# AntiStartingCrap.net
KiCad netlist of a schematic drawn in Altium Designer
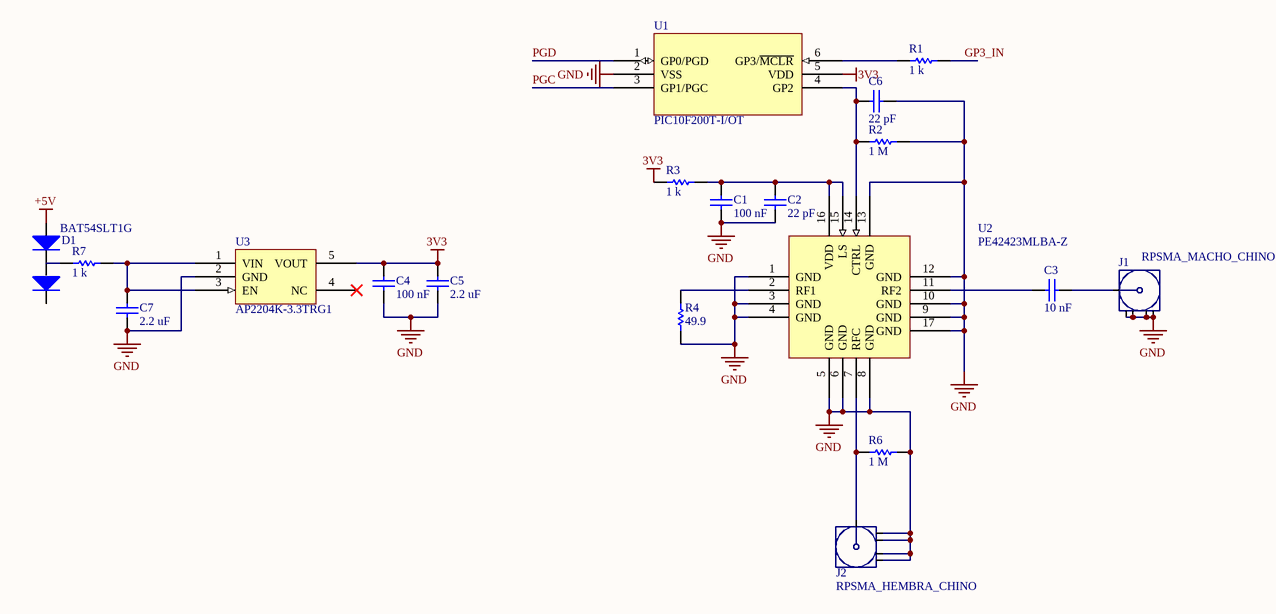
[diagram p0: AntiStartingCrap.SchDoc]

(export (version "E")
  (design (tool "Eeschema 10.0.6"))
  (components
    (comp (ref "C1")
      (value "100 nF")
      (footprint "CAPC1608X10L")
      (description "CAP CER 0.1UF 25V X7R 0603")
      (fields
        (field (name "MANUFACTURER") "Samsung Electro-Mechanics America, Inc.")
        (field (name "MANUFACTURER PART NUMBER") "CL10B104KA8NNNC")
      )
      (libsource (lib "Componentes") (part "CL10B104KA8NNNC"))
    )
    (comp (ref "C2")
      (value "22 pF")
      (footprint "CAPC1608X10L")
      (description "CAP CER 22PF 50V NP0 0603")
      (fields
        (field (name "MANUFACTURER") "Murata Electronics North America")
        (field (name "MANUFACTURER PART NUMBER") "GCM1885C1H220JA16D")
      )
      (libsource (lib "Componentes") (part "GCM1885C1H220JA16D"))
    )
    (comp (ref "C3")
      (value "10 nF")
      (footprint "CAPC1608X10L")
      (description "CAP CER 10000PF 50V NP0 0603")
      (fields
        (field (name "MANUFACTURER") "Murata Electronics North America")
        (field (name "MANUFACTURER PART NUMBER") "GRM1885C1H103JA01D")
      )
      (libsource (lib "Componentes") (part "GRM1885C1H103JA01D"))
    )
    (comp (ref "C4")
      (value "100 nF")
      (footprint "CAPC1608X10L")
      (description "CAP CER 0.1UF 25V X7R 0603")
      (fields
        (field (name "MANUFACTURER") "Samsung Electro-Mechanics America, Inc.")
        (field (name "MANUFACTURER PART NUMBER") "CL10B104KA8NNNC")
      )
      (libsource (lib "Componentes") (part "CL10B104KA8NNNC"))
    )
    (comp (ref "C5")
      (value "2.2 uF")
      (footprint "CAPC1608X10L")
      (description "CAP CER 2.2UF 25V X5R 0603")
      (fields
        (field (name "MANUFACTURER") "Murata Electronics North America")
        (field (name "MANUFACTURER PART NUMBER") "GRM188R61E225MA12D")
      )
      (libsource (lib "Componentes") (part "GRM188R61E225MA12D"))
    )
    (comp (ref "C6")
      (value "22 pF")
      (footprint "CAPC1608X10L")
      (description "CAP CER 22PF 50V NP0 0603")
      (fields
        (field (name "MANUFACTURER") "Murata Electronics North America")
        (field (name "MANUFACTURER PART NUMBER") "GCM1885C1H220JA16D")
      )
      (libsource (lib "Componentes") (part "GCM1885C1H220JA16D"))
    )
    (comp (ref "C7")
      (value "2.2 uF")
      (footprint "CAPC1608X10L")
      (description "CAP CER 2.2UF 25V X5R 0603")
      (fields
        (field (name "MANUFACTURER") "Murata Electronics North America")
        (field (name "MANUFACTURER PART NUMBER") "GRM188R61E225MA12D")
      )
      (libsource (lib "Componentes") (part "GRM188R61E225MA12D"))
    )
    (comp (ref "D1")
      (value "BAT54SLT1G")
      (footprint "SOT95P237X111-3N")
      (description "Schottky Diodes & Rectifiers 30V 225mW Dual")
      (fields (field (name "MANUFACTURER") "ON Semiconductor"))
      (libsource (lib "Componentes") (part "BAT54SLT1G"))
    )
    (comp (ref "J1")
      (value "RPSMA_MACHO_CHINO")
      (footprint "SMACHINO")
      (libsource (lib "Components") (part "RPSMA_MACHO_CHINO"))
    )
    (comp (ref "J2")
      (value "RPSMA_HEMBRA_CHINO")
      (footprint "SMACHINO")
      (libsource (lib "Components") (part "RPSMA_HEMBRA_CHINO"))
    )
    (comp (ref "R1")
      (value "1 k")
      (footprint "RESC1608X05N")
      (description "Thick Film Resistors - SMD 1/10watt 1.0Kohms 1%")
      (fields
        (field (name "MANUFACTURER") "Vishay / Dale")
        (field (name "MANUFACTURER PART NUMBER") "CRCW06031K00FKEA")
      )
      (libsource (lib "Componentes") (part "CRCW06031K00FKEA"))
    )
    (comp (ref "R2")
      (value "1 M")
      (footprint "RESC1608X05N")
      (description "Thick Film Resistors - SMD 1/10watt 1.0Mohms 1%")
      (fields
        (field (name "MANUFACTURER") "Vishay / Dale")
        (field (name "MANUFACTURER PART NUMBER") "CRCW06031M00FKEA")
      )
      (libsource (lib "Componentes") (part "CRCW06031M00FKEA"))
    )
    (comp (ref "R3")
      (value "1 k")
      (footprint "RESC1608X05N")
      (description "Thick Film Resistors - SMD 1/10watt 1.0Kohms 1%")
      (fields
        (field (name "MANUFACTURER") "Vishay / Dale")
        (field (name "MANUFACTURER PART NUMBER") "CRCW06031K00FKEA")
      )
      (libsource (lib "Componentes") (part "CRCW06031K00FKEA"))
    )
    (comp (ref "R4")
      (value "49.9")
      (footprint "RESC1608X05N")
      (description "RES SMD 49.9 OHM 1% 1/10W 0603")
      (fields
        (field (name "MANUFACTURER") "Vishay Dale")
        (field (name "MANUFACTURER PART NUMBER") "CRCW060349R9FKEA")
      )
      (libsource (lib "Componentes") (part "CRCW060349R9FKEA"))
    )
    (comp (ref "R6")
      (value "1 M")
      (footprint "RESC1608X05N")
      (description "Thick Film Resistors - SMD 1/10watt 1.0Mohms 1%")
      (fields
        (field (name "MANUFACTURER") "Vishay / Dale")
        (field (name "MANUFACTURER PART NUMBER") "CRCW06031M00FKEA")
      )
      (libsource (lib "Componentes") (part "CRCW06031M00FKEA"))
    )
    (comp (ref "R7")
      (value "1 k")
      (footprint "RESC1608X05N")
      (description "Thick Film Resistors - SMD 1/10watt 1.0Kohms 1%")
      (fields
        (field (name "MANUFACTURER") "Vishay / Dale")
        (field (name "MANUFACTURER PART NUMBER") "CRCW06031K00FKEA")
      )
      (libsource (lib "Componentes") (part "CRCW06031K00FKEA"))
    )
    (comp (ref "U1")
      (value "PIC10F200T-I/OT")
      (footprint "SOT95P270X145-6N")
      (description "IC MCU 8BIT 384B FLASH SOT23-6")
      (fields (field (name "MANUFACTURER") "Microchip Technology"))
      (libsource (lib "Components") (part "PIC10F200T-I/OT"))
    )
    (comp (ref "U2")
      (value "PE42423MLBA-Z")
      (footprint "QFN50P300X300X90_HS-17N _PEREGRINE")
      (description "IC RF SWITCH SPDT 50 OHM 16QFN")
      (fields (field (name "MANUFACTURER") "Peregrine Semiconductor"))
      (libsource (lib "Components") (part "PE42423MLBA-Z"))
    )
    (comp (ref "U3")
      (value "AP2204K-3.3TRG1")
      (footprint "SOT95P270X145-5N")
      (description "IC REG LDO 3.3V 0.15A SOT25")
      (fields (field (name "MANUFACTURER") "Diodes Incorporated"))
      (libsource (lib "Components") (part "AP2204K-3.3TRG1"))
    )
  )
  (nets
    (net (code "1") (name "+5V") (class "Default")
      (node (ref "D1") (pin "1") (pinfunction "A_1") (pintype "passive"))
    )
    (net (code "2") (name "/GP3_IN") (class "Default")
      (node (ref "R1") (pin "2") (pinfunction "2_2") (pintype "passive"))
    )
    (net (code "3") (name "/PGC") (class "Default")
      (node (ref "U1") (pin "3") (pinfunction "GP1/PGC_3") (pintype "power_in"))
    )
    (net (code "4") (name "/PGD") (class "Default")
      (node (ref "U1") (pin "1") (pinfunction "GP0/PGD_1") (pintype "bidirectional"))
    )
    (net (code "5") (name "3V3") (class "Default")
      (node (ref "C4") (pin "2") (pinfunction "2_2") (pintype "passive"))
      (node (ref "C5") (pin "2") (pinfunction "2_2") (pintype "passive"))
      (node (ref "R3") (pin "1") (pinfunction "1_1") (pintype "passive"))
      (node (ref "U1") (pin "5") (pinfunction "VDD_5") (pintype "power_in"))
      (node (ref "U3") (pin "5") (pinfunction "VOUT_5") (pintype "power_in"))
    )
    (net (code "6") (name "GND") (class "Default")
      (node (ref "C1") (pin "1") (pinfunction "1_1") (pintype "passive"))
      (node (ref "C2") (pin "1") (pinfunction "1_1") (pintype "passive"))
      (node (ref "C4") (pin "1") (pinfunction "1_1") (pintype "passive"))
      (node (ref "C5") (pin "1") (pinfunction "1_1") (pintype "passive"))
      (node (ref "C6") (pin "1") (pinfunction "1_1") (pintype "passive"))
      (node (ref "C7") (pin "1") (pinfunction "1_1") (pintype "passive"))
      (node (ref "J1") (pin "2") (pinfunction "2_2") (pintype "passive"))
      (node (ref "J1") (pin "3") (pinfunction "3_3") (pintype "passive"))
      (node (ref "J1") (pin "4") (pinfunction "4_4") (pintype "passive"))
      (node (ref "J1") (pin "5") (pinfunction "5_5") (pintype "passive"))
      (node (ref "J2") (pin "2") (pinfunction "2_2") (pintype "passive"))
      (node (ref "J2") (pin "3") (pinfunction "3_3") (pintype "passive"))
      (node (ref "J2") (pin "4") (pinfunction "4_4") (pintype "passive"))
      (node (ref "J2") (pin "5") (pinfunction "5_5") (pintype "passive"))
      (node (ref "R2") (pin "2") (pinfunction "2_2") (pintype "passive"))
      (node (ref "R4") (pin "2") (pinfunction "2_2") (pintype "passive"))
      (node (ref "R6") (pin "2") (pinfunction "2_2") (pintype "passive"))
      (node (ref "U1") (pin "2") (pinfunction "VSS_2") (pintype "power_in"))
      (node (ref "U2") (pin "1") (pinfunction "GND_1") (pintype "power_in"))
      (node (ref "U2") (pin "10") (pinfunction "GND_10") (pintype "power_in"))
      (node (ref "U2") (pin "12") (pinfunction "GND_12") (pintype "power_in"))
      (node (ref "U2") (pin "13") (pinfunction "GND_13") (pintype "power_in"))
      (node (ref "U2") (pin "17") (pinfunction "GND_17") (pintype "power_in"))
      (node (ref "U2") (pin "3") (pinfunction "GND_3") (pintype "power_in"))
      (node (ref "U2") (pin "4") (pinfunction "GND_4") (pintype "power_in"))
      (node (ref "U2") (pin "5") (pinfunction "GND_5") (pintype "power_in"))
      (node (ref "U2") (pin "6") (pinfunction "GND_6") (pintype "power_in"))
      (node (ref "U2") (pin "8") (pinfunction "GND_8") (pintype "power_in"))
      (node (ref "U2") (pin "9") (pinfunction "GND_9") (pintype "power_in"))
      (node (ref "U3") (pin "2") (pinfunction "GND_2") (pintype "power_in"))
    )
    (net (code "7") (name "Net-(C3-Pad1)") (class "Default")
      (node (ref "C3") (pin "1") (pinfunction "1_1") (pintype "passive"))
      (node (ref "J1") (pin "1") (pinfunction "1_1") (pintype "passive"))
    )
    (net (code "8") (name "Net-(D1-C)") (class "Default")
      (node (ref "D1") (pin "3") (pinfunction "C_3") (pintype "passive"))
      (node (ref "R7") (pin "1") (pinfunction "1_1") (pintype "passive"))
    )
    (net (code "9") (name "Net-(U1-GP2)") (class "Default")
      (node (ref "C6") (pin "2") (pinfunction "2_2") (pintype "passive"))
      (node (ref "R2") (pin "1") (pinfunction "1_1") (pintype "passive"))
      (node (ref "U1") (pin "4") (pinfunction "GP2_4") (pintype "power_in"))
      (node (ref "U2") (pin "14") (pinfunction "CTRL_14") (pintype "input"))
    )
    (net (code "10") (name "Net-(U1-GP3{slash}~{MCLR})") (class "Default")
      (node (ref "R1") (pin "1") (pinfunction "1_1") (pintype "passive"))
      (node (ref "U1") (pin "6") (pinfunction "GP3/~{MCLR}_6") (pintype "input"))
    )
    (net (code "11") (name "Net-(U2-LS)") (class "Default")
      (node (ref "C1") (pin "2") (pinfunction "2_2") (pintype "passive"))
      (node (ref "C2") (pin "2") (pinfunction "2_2") (pintype "passive"))
      (node (ref "R3") (pin "2") (pinfunction "2_2") (pintype "passive"))
      (node (ref "U2") (pin "15") (pinfunction "LS_15") (pintype "input"))
      (node (ref "U2") (pin "16") (pinfunction "VDD_16") (pintype "power_in"))
    )
    (net (code "12") (name "Net-(U2-RF1)") (class "Default")
      (node (ref "R4") (pin "1") (pinfunction "1_1") (pintype "passive"))
      (node (ref "U2") (pin "2") (pinfunction "RF1_2") (pintype "passive"))
    )
    (net (code "13") (name "Net-(U2-RF2)") (class "Default")
      (node (ref "C3") (pin "2") (pinfunction "2_2") (pintype "passive"))
      (node (ref "U2") (pin "11") (pinfunction "RF2_11") (pintype "passive"))
    )
    (net (code "14") (name "Net-(U2-RFC)") (class "Default")
      (node (ref "J2") (pin "1") (pinfunction "1_1") (pintype "passive"))
      (node (ref "R6") (pin "1") (pinfunction "1_1") (pintype "passive"))
      (node (ref "U2") (pin "7") (pinfunction "RFC_7") (pintype "passive"))
    )
    (net (code "15") (name "Net-(U3-EN)") (class "Default")
      (node (ref "C7") (pin "2") (pinfunction "2_2") (pintype "passive"))
      (node (ref "R7") (pin "2") (pinfunction "2_2") (pintype "passive"))
      (node (ref "U3") (pin "1") (pinfunction "VIN_1") (pintype "power_in"))
      (node (ref "U3") (pin "3") (pinfunction "EN_3") (pintype "input"))
    )
    (net (code "16") (name "unconnected-(D1-K-Pad2)") (class "Default")
      (node (ref "D1") (pin "2") (pinfunction "K_2") (pintype "passive"))
    )
    (net (code "17") (name "unconnected-(U3-NC-Pad4)") (class "Default")
      (node (ref "U3") (pin "4") (pinfunction "NC_4") (pintype "passive+no_connect"))
    )
  )
)
